# int_esp_8266.net
KiCad netlist of a schematic drawn in EAGLE
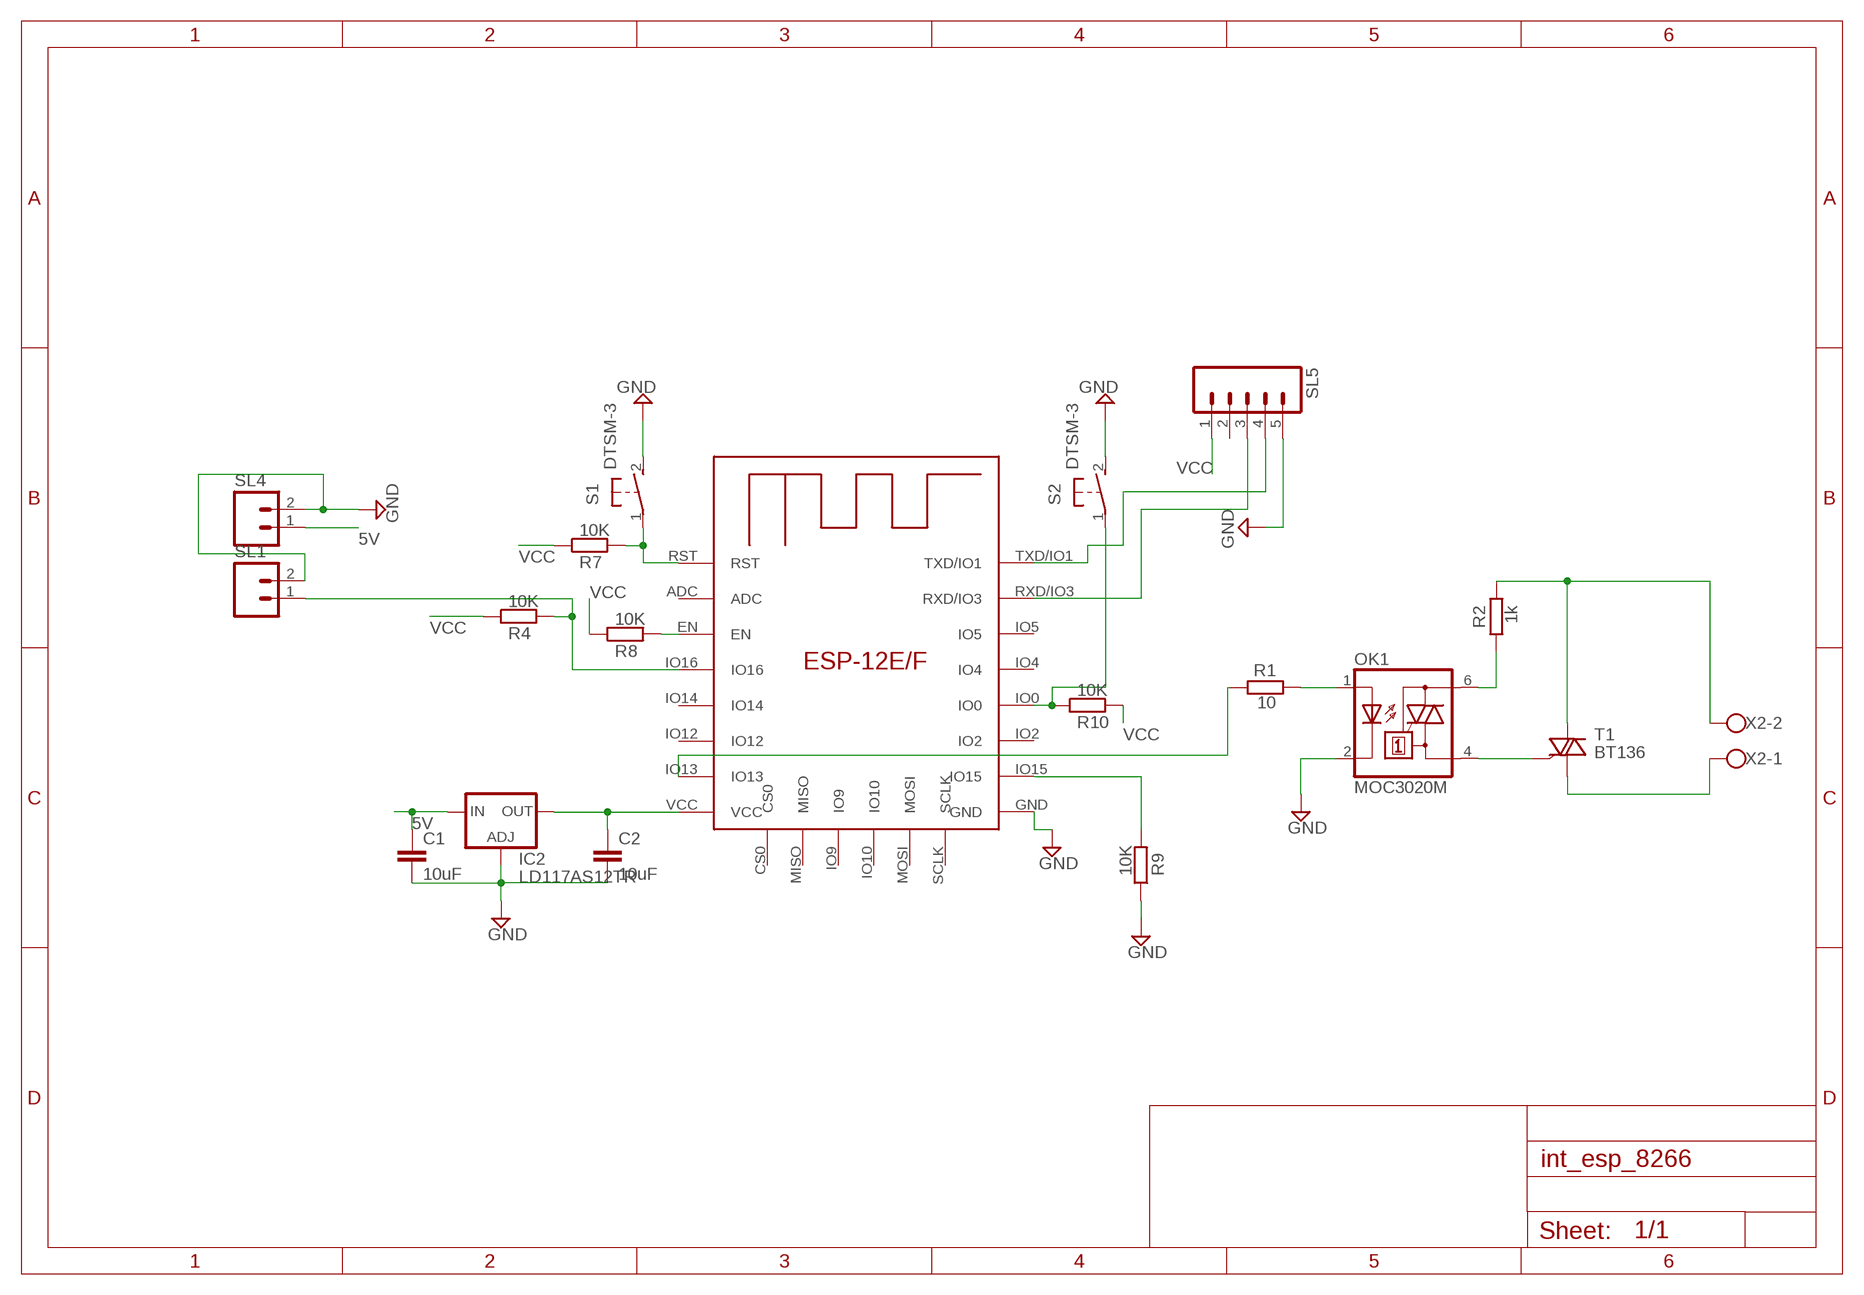
[diagram p0: schematic, sheet 1]

(export (version "E")
  (design (tool "Eeschema 10.0.6"))
  (components
    (comp (ref "C1")
      (value "10uF")
      (footprint "eagle-import:C0805")
      (libsource (lib "eagle-import") (part "C-EUC0805"))
    )
    (comp (ref "C2")
      (value "10uF")
      (footprint "eagle-import:C0805")
      (libsource (lib "eagle-import") (part "C-EUC0805"))
    )
    (comp (ref "IC1")
      (value "ESP-12E/F")
      (footprint "eagle-import:ESP-12E")
      (libsource (lib "eagle-import") (part "ESP-12E/F"))
    )
    (comp (ref "IC2")
      (value "LD117AS12TR")
      (footprint "eagle-import:SOT223")
      (libsource (lib "eagle-import") (part "LD117A?S12TR"))
    )
    (comp (ref "OK1")
      (value "MOC3020M")
      (footprint "eagle-import:DIL06")
      (fields (field (name "MF") "FAIRCHILD SEMICONDUCTOR") (field (name "MPN") "MOC3020-M"))
      (libsource (lib "eagle-import") (part "MOC30M20"))
    )
    (comp (ref "R1")
      (value "10")
      (footprint "eagle-import:M0805")
      (libsource (lib "eagle-import") (part "R-EU_M0805"))
    )
    (comp (ref "R2")
      (value "1k")
      (footprint "eagle-import:M0805")
      (libsource (lib "eagle-import") (part "R-EU_M0805"))
    )
    (comp (ref "R4")
      (value "10K")
      (footprint "eagle-import:M0805")
      (libsource (lib "eagle-import") (part "R-EU_M0805"))
    )
    (comp (ref "R7")
      (value "10K")
      (footprint "eagle-import:M0805")
      (libsource (lib "eagle-import") (part "R-EU_M0805"))
    )
    (comp (ref "R8")
      (value "10K")
      (footprint "eagle-import:M0805")
      (libsource (lib "eagle-import") (part "R-EU_M0805"))
    )
    (comp (ref "R9")
      (value "10K")
      (footprint "eagle-import:M0805")
      (libsource (lib "eagle-import") (part "R-EU_M0805"))
    )
    (comp (ref "R10")
      (value "10K")
      (footprint "eagle-import:M0805")
      (libsource (lib "eagle-import") (part "R-EU_M0805"))
    )
    (comp (ref "S1")
      (value "DTSM-3")
      (footprint "eagle-import:DTSM-3")
      (libsource (lib "eagle-import") (part "DTSM-3"))
    )
    (comp (ref "S2")
      (value "DTSM-3")
      (footprint "eagle-import:DTSM-3")
      (libsource (lib "eagle-import") (part "DTSM-3"))
    )
    (comp (ref "SL1")
      (value "M02")
      (footprint "eagle-import:02P")
      (libsource (lib "eagle-import") (part "M02"))
    )
    (comp (ref "SL4")
      (value "M02")
      (footprint "eagle-import:02P")
      (libsource (lib "eagle-import") (part "M02"))
    )
    (comp (ref "SL5")
      (value "M05")
      (footprint "eagle-import:05P")
      (libsource (lib "eagle-import") (part "M05"))
    )
    (comp (ref "T1")
      (value "BT136")
      (footprint "eagle-import:TO220AB")
      (libsource (lib "eagle-import") (part "BT136"))
    )
    (comp (ref "X2")
      (value "W237-102")
      (footprint "eagle-import:W237-102")
      (fields (field (name "MPN") "237-102"))
      (libsource (lib "eagle-import") (part "W237-102"))
    )
  )
  (nets
    (net (code "1") (name "/5V") (class "Default")
      (node (ref "C1") (pin "1") (pinfunction "1_1") (pintype "passive"))
      (node (ref "IC2") (pin "3") (pinfunction "IN_3") (pintype "input"))
      (node (ref "SL4") (pin "1") (pinfunction "1_1") (pintype "passive"))
    )
    (net (code "2") (name "/VCC") (class "Default")
      (node (ref "C2") (pin "1") (pinfunction "1_1") (pintype "passive"))
      (node (ref "IC1") (pin "VCC") (pinfunction "VCC_VCC") (pintype "power_in"))
      (node (ref "IC2") (pin "4") (pinfunction "OUT_4") (pintype "passive"))
      (node (ref "R10") (pin "2") (pinfunction "2_2") (pintype "passive"))
      (node (ref "R4") (pin "1") (pinfunction "1_1") (pintype "passive"))
      (node (ref "R7") (pin "1") (pinfunction "1_1") (pintype "passive"))
      (node (ref "R8") (pin "1") (pinfunction "1_1") (pintype "passive"))
      (node (ref "SL5") (pin "1") (pinfunction "1_1") (pintype "passive"))
    )
    (net (code "3") (name "GND") (class "Default")
      (node (ref "C1") (pin "2") (pinfunction "2_2") (pintype "passive"))
      (node (ref "C2") (pin "2") (pinfunction "2_2") (pintype "passive"))
      (node (ref "IC1") (pin "GND") (pinfunction "GND_GND") (pintype "power_in"))
      (node (ref "IC2") (pin "1") (pinfunction "ADJ_1") (pintype "input"))
      (node (ref "OK1") (pin "2") (pinfunction "C_2") (pintype "passive"))
      (node (ref "R9") (pin "1") (pinfunction "1_1") (pintype "passive"))
      (node (ref "S1") (pin "2") (pinfunction "2_2") (pintype "passive"))
      (node (ref "S2") (pin "2") (pinfunction "2_2") (pintype "passive"))
      (node (ref "SL1") (pin "2") (pinfunction "2_2") (pintype "passive"))
      (node (ref "SL4") (pin "2") (pinfunction "2_2") (pintype "passive"))
      (node (ref "SL5") (pin "5") (pinfunction "5_5") (pintype "passive"))
    )
    (net (code "4") (name "Net-(IC1-PadEN)") (class "Default")
      (node (ref "IC1") (pin "EN") (pinfunction "EN_EN") (pintype "bidirectional"))
      (node (ref "R8") (pin "2") (pinfunction "2_2") (pintype "passive"))
    )
    (net (code "5") (name "Net-(IC1-PadIO0)") (class "Default")
      (node (ref "IC1") (pin "IO0") (pinfunction "IO0_IO0") (pintype "bidirectional"))
      (node (ref "R10") (pin "1") (pinfunction "1_1") (pintype "passive"))
      (node (ref "S2") (pin "1") (pinfunction "1_1") (pintype "passive"))
    )
    (net (code "6") (name "Net-(IC1-PadIO13)") (class "Default")
      (node (ref "IC1") (pin "IO13") (pinfunction "IO13_IO13") (pintype "bidirectional"))
      (node (ref "R1") (pin "2") (pinfunction "2_2") (pintype "passive"))
    )
    (net (code "7") (name "Net-(IC1-PadIO15)") (class "Default")
      (node (ref "IC1") (pin "IO15") (pinfunction "IO15_IO15") (pintype "bidirectional"))
      (node (ref "R9") (pin "2") (pinfunction "2_2") (pintype "passive"))
    )
    (net (code "8") (name "Net-(IC1-PadIO16)") (class "Default")
      (node (ref "IC1") (pin "IO16") (pinfunction "IO16_IO16") (pintype "bidirectional"))
      (node (ref "R4") (pin "2") (pinfunction "2_2") (pintype "passive"))
      (node (ref "SL1") (pin "1") (pinfunction "1_1") (pintype "passive"))
    )
    (net (code "9") (name "Net-(IC1-PadRST)") (class "Default")
      (node (ref "IC1") (pin "RST") (pinfunction "RST_RST") (pintype "input"))
      (node (ref "R7") (pin "2") (pinfunction "2_2") (pintype "passive"))
      (node (ref "S1") (pin "1") (pinfunction "1_1") (pintype "passive"))
    )
    (net (code "10") (name "Net-(IC1-PadRXD{slash}IO3)") (class "Default")
      (node (ref "IC1") (pin "RXD/IO3") (pinfunction "RXD/IO3_RXD/IO3") (pintype "bidirectional"))
      (node (ref "SL5") (pin "3") (pinfunction "3_3") (pintype "passive"))
    )
    (net (code "11") (name "Net-(IC1-PadTXD{slash}IO1)") (class "Default")
      (node (ref "IC1") (pin "TXD/IO1") (pinfunction "TXD/IO1_TXD/IO1") (pintype "bidirectional"))
      (node (ref "SL5") (pin "4") (pinfunction "4_4") (pintype "passive"))
    )
    (net (code "12") (name "Net-(OK1-A)") (class "Default")
      (node (ref "OK1") (pin "1") (pinfunction "A_1") (pintype "passive"))
      (node (ref "R1") (pin "1") (pinfunction "1_1") (pintype "passive"))
    )
    (net (code "13") (name "Net-(OK1-A1)") (class "Default")
      (node (ref "OK1") (pin "4") (pinfunction "A1_4") (pintype "passive"))
      (node (ref "T1") (pin "3") (pinfunction "G_3") (pintype "passive"))
    )
    (net (code "14") (name "Net-(OK1-A2)") (class "Default")
      (node (ref "OK1") (pin "6") (pinfunction "A2_6") (pintype "passive"))
      (node (ref "R2") (pin "2") (pinfunction "2_2") (pintype "passive"))
    )
    (net (code "15") (name "Net-(T1-A1)") (class "Default")
      (node (ref "T1") (pin "1") (pinfunction "A1_1") (pintype "passive"))
      (node (ref "X2") (pin "1") (pinfunction "KL_1") (pintype "passive"))
    )
    (net (code "16") (name "Net-(T1-A2)") (class "Default")
      (node (ref "R2") (pin "1") (pinfunction "1_1") (pintype "passive"))
      (node (ref "T1") (pin "2") (pinfunction "A2_2") (pintype "passive"))
      (node (ref "X2") (pin "2") (pinfunction "KL_2") (pintype "passive"))
    )
    (net (code "17") (name "unconnected-(IC1-PadADC)") (class "Default")
      (node (ref "IC1") (pin "ADC") (pinfunction "ADC_ADC") (pintype "bidirectional"))
    )
    (net (code "18") (name "unconnected-(IC1-PadCS0)") (class "Default")
      (node (ref "IC1") (pin "CS0") (pinfunction "CS0_CS0") (pintype "bidirectional"))
    )
    (net (code "19") (name "unconnected-(IC1-PadIO2)") (class "Default")
      (node (ref "IC1") (pin "IO2") (pinfunction "IO2_IO2") (pintype "bidirectional"))
    )
    (net (code "20") (name "unconnected-(IC1-PadIO4)") (class "Default")
      (node (ref "IC1") (pin "IO4") (pinfunction "IO4_IO4") (pintype "bidirectional"))
    )
    (net (code "21") (name "unconnected-(IC1-PadIO5)") (class "Default")
      (node (ref "IC1") (pin "IO5") (pinfunction "IO5_IO5") (pintype "bidirectional"))
    )
    (net (code "22") (name "unconnected-(IC1-PadIO9)") (class "Default")
      (node (ref "IC1") (pin "IO9") (pinfunction "IO9_IO9") (pintype "bidirectional"))
    )
    (net (code "23") (name "unconnected-(IC1-PadIO10)") (class "Default")
      (node (ref "IC1") (pin "IO10") (pinfunction "IO10_IO10") (pintype "bidirectional"))
    )
    (net (code "24") (name "unconnected-(IC1-PadIO12)") (class "Default")
      (node (ref "IC1") (pin "IO12") (pinfunction "IO12_IO12") (pintype "bidirectional"))
    )
    (net (code "25") (name "unconnected-(IC1-PadIO14)") (class "Default")
      (node (ref "IC1") (pin "IO14") (pinfunction "IO14_IO14") (pintype "bidirectional"))
    )
    (net (code "26") (name "unconnected-(IC1-PadMISO)") (class "Default")
      (node (ref "IC1") (pin "MISO") (pinfunction "MISO_MISO") (pintype "bidirectional"))
    )
    (net (code "27") (name "unconnected-(IC1-PadMOSI)") (class "Default")
      (node (ref "IC1") (pin "MOSI") (pinfunction "MOSI_MOSI") (pintype "bidirectional"))
    )
    (net (code "28") (name "unconnected-(IC1-PadSCLK)") (class "Default")
      (node (ref "IC1") (pin "SCLK") (pinfunction "SCLK_SCLK") (pintype "bidirectional"))
    )
    (net (code "29") (name "unconnected-(SL5-Pad2)") (class "Default")
      (node (ref "SL5") (pin "2") (pinfunction "2_2") (pintype "passive"))
    )
  )
)
